# main_board.net
KiCad netlist of a schematic drawn in EAGLE
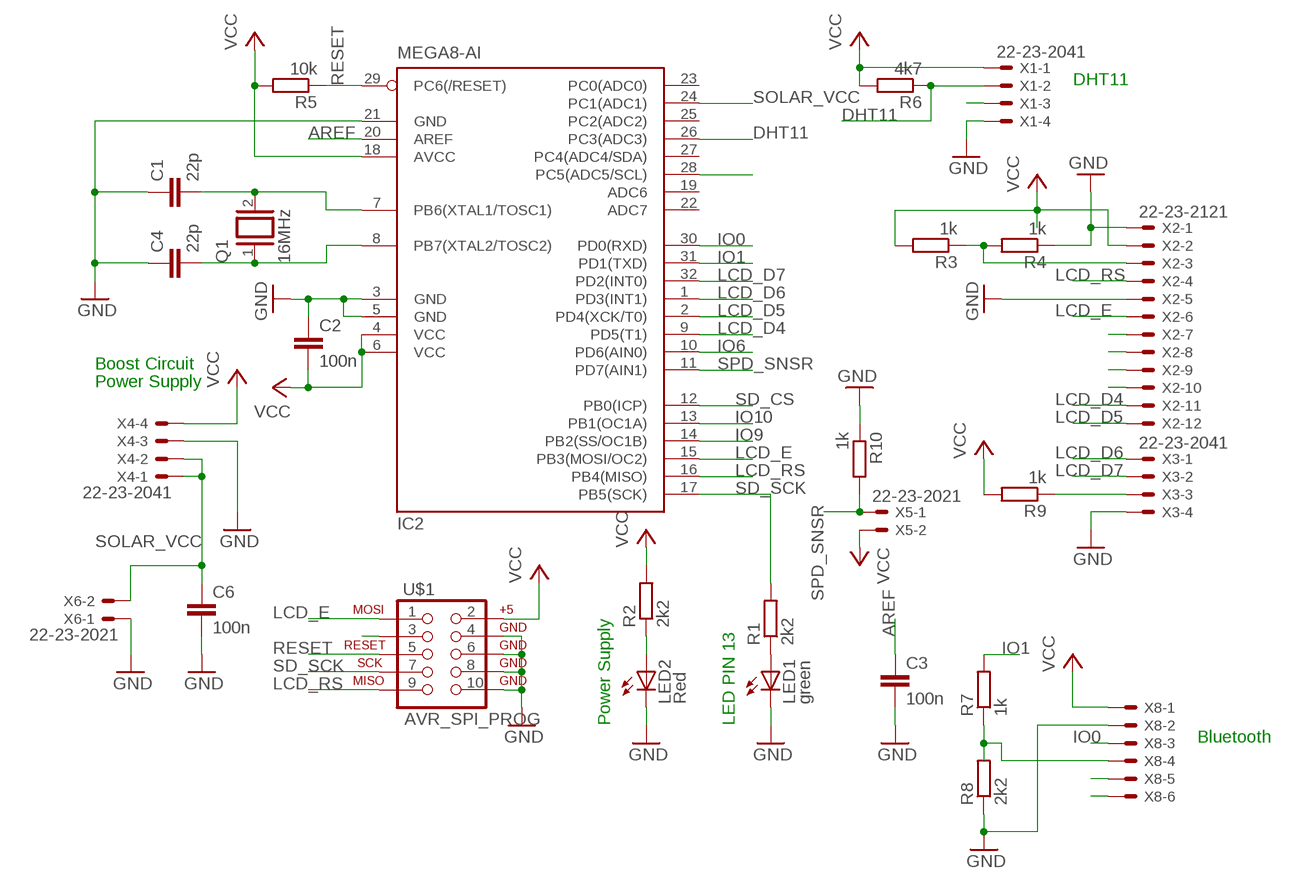
[diagram p0: schematic, sheet 1]

(export (version "E")
  (design (tool "Eeschema 10.0.6"))
  (components
    (comp (ref "C1")
      (value "22p")
      (footprint "eagle-import:C2.5-3")
      (libsource (lib "eagle-import") (part "C2,5-3"))
    )
    (comp (ref "C2")
      (value "100n")
      (footprint "eagle-import:C5B3")
      (libsource (lib "eagle-import") (part "C5/3"))
    )
    (comp (ref "C3")
      (value "100n")
      (footprint "eagle-import:C5B3")
      (libsource (lib "eagle-import") (part "C5/3"))
    )
    (comp (ref "C4")
      (value "22p")
      (footprint "eagle-import:C2.5-3")
      (libsource (lib "eagle-import") (part "C2,5-3"))
    )
    (comp (ref "C6")
      (value "100n")
      (footprint "eagle-import:C7.5B6")
      (libsource (lib "eagle-import") (part "C7.5/6"))
    )
    (comp (ref "IC2")
      (value "MEGA8-AI")
      (footprint "eagle-import:TQFP32-08")
      (fields (field (name "MPN") "ATMEGA8-16AU"))
      (libsource (lib "eagle-import") (part "MEGA8-AI"))
    )
    (comp (ref "LED1")
      (value "green")
      (footprint "eagle-import:LED3MM")
      (libsource (lib "eagle-import") (part "LED3MM"))
    )
    (comp (ref "LED2")
      (value "Red")
      (footprint "eagle-import:LED3MM")
      (libsource (lib "eagle-import") (part "LED3MM"))
    )
    (comp (ref "Q1")
      (value "16MHz")
      (footprint "eagle-import:QS")
      (libsource (lib "eagle-import") (part "XTAL/S"))
    )
    (comp (ref "R1")
      (value "2k2")
      (footprint "eagle-import:0204V")
      (libsource (lib "eagle-import") (part "R-EU_0204/2V"))
    )
    (comp (ref "R2")
      (value "2k2")
      (footprint "eagle-import:0204V")
      (libsource (lib "eagle-import") (part "R-EU_0204/2V"))
    )
    (comp (ref "R3")
      (value "1k")
      (footprint "eagle-import:0204V")
      (libsource (lib "eagle-import") (part "R-EU_0204/2V"))
    )
    (comp (ref "R4")
      (value "1k")
      (footprint "eagle-import:0204V")
      (libsource (lib "eagle-import") (part "R-EU_0204/2V"))
    )
    (comp (ref "R5")
      (value "10k")
      (footprint "eagle-import:0204V")
      (libsource (lib "eagle-import") (part "R-EU_0204/2V"))
    )
    (comp (ref "R6")
      (value "4k7")
      (footprint "eagle-import:0204V")
      (libsource (lib "eagle-import") (part "R-EU_0204/2V"))
    )
    (comp (ref "R7")
      (value "1k")
      (footprint "eagle-import:0204V")
      (libsource (lib "eagle-import") (part "R-EU_0204/2V"))
    )
    (comp (ref "R8")
      (value "2k2")
      (footprint "eagle-import:0204V")
      (libsource (lib "eagle-import") (part "R-EU_0204/2V"))
    )
    (comp (ref "R9")
      (value "1k")
      (footprint "eagle-import:0204V")
      (libsource (lib "eagle-import") (part "R-EU_0204/2V"))
    )
    (comp (ref "R10")
      (value "1k")
      (footprint "eagle-import:0204V")
      (libsource (lib "eagle-import") (part "R-EU_0204/2V"))
    )
    (comp (ref "U$1")
      (value "AVR_SPI_PROG")
      (footprint "eagle-import:AVR_ICSP")
      (libsource (lib "eagle-import") (part "AVR_SPI_PROG"))
    )
    (comp (ref "X1")
      (value "22-23-2041")
      (footprint "eagle-import:22-23-2041")
      (fields (field (name "MF") "MOLEX"))
      (libsource (lib "eagle-import") (part "22-23-2041"))
    )
    (comp (ref "X2")
      (value "22-23-2121")
      (footprint "eagle-import:22-23-2121")
      (fields (field (name "MF") "MOLEX"))
      (libsource (lib "eagle-import") (part "22-23-2121"))
    )
    (comp (ref "X3")
      (value "22-23-2041")
      (footprint "eagle-import:22-23-2041")
      (fields (field (name "MF") "MOLEX"))
      (libsource (lib "eagle-import") (part "22-23-2041"))
    )
    (comp (ref "X4")
      (value "22-23-2041")
      (footprint "eagle-import:22-23-2041")
      (fields (field (name "MF") "MOLEX"))
      (libsource (lib "eagle-import") (part "22-23-2041"))
    )
    (comp (ref "X5")
      (value "22-23-2021")
      (footprint "eagle-import:22-23-2021")
      (fields (field (name "MF") "MOLEX"))
      (libsource (lib "eagle-import") (part "22-23-2021"))
    )
    (comp (ref "X6")
      (value "22-23-2021")
      (footprint "eagle-import:22-23-2021")
      (fields (field (name "MF") "MOLEX"))
      (libsource (lib "eagle-import") (part "22-23-2021"))
    )
    (comp (ref "X8")
      (value "22-23-2061")
      (footprint "eagle-import:22-23-2061")
      (fields (field (name "MF") "MOLEX"))
      (libsource (lib "eagle-import") (part "22-23-2061"))
    )
  )
  (nets
    (net (code "1") (name "/AREF") (class "Default")
      (node (ref "C3") (pin "1") (pinfunction "1_1") (pintype "passive"))
      (node (ref "IC2") (pin "20") (pinfunction "AREF_20") (pintype "passive"))
    )
    (net (code "2") (name "/DHT11") (class "Default")
      (node (ref "IC2") (pin "26") (pinfunction "PC3(ADC3)_26") (pintype "bidirectional"))
      (node (ref "R6") (pin "1") (pinfunction "1_1") (pintype "passive"))
      (node (ref "X1") (pin "2") (pinfunction "S_2") (pintype "passive"))
    )
    (net (code "3") (name "/IO0") (class "Default")
      (node (ref "IC2") (pin "30") (pinfunction "PD0(RXD)_30") (pintype "bidirectional"))
      (node (ref "X8") (pin "3") (pinfunction "S_3") (pintype "passive"))
    )
    (net (code "4") (name "/IO1") (class "Default")
      (node (ref "IC2") (pin "31") (pinfunction "PD1(TXD)_31") (pintype "bidirectional"))
      (node (ref "R7") (pin "2") (pinfunction "2_2") (pintype "passive"))
    )
    (net (code "5") (name "/IO6") (class "Default")
      (node (ref "IC2") (pin "10") (pinfunction "PD6(AIN0)_10") (pintype "bidirectional"))
    )
    (net (code "6") (name "/IO9") (class "Default")
      (node (ref "IC2") (pin "14") (pinfunction "PB2(SS/OC1B)_14") (pintype "bidirectional"))
    )
    (net (code "7") (name "/IO10") (class "Default")
      (node (ref "IC2") (pin "13") (pinfunction "PB1(OC1A)_13") (pintype "bidirectional"))
    )
    (net (code "8") (name "/LCD_D4") (class "Default")
      (node (ref "IC2") (pin "9") (pinfunction "PD5(T1)_9") (pintype "bidirectional"))
      (node (ref "X2") (pin "11") (pinfunction "S_11") (pintype "passive"))
    )
    (net (code "9") (name "/LCD_D5") (class "Default")
      (node (ref "IC2") (pin "2") (pinfunction "PD4(XCK/T0)_2") (pintype "bidirectional"))
      (node (ref "X2") (pin "12") (pinfunction "S_12") (pintype "passive"))
    )
    (net (code "10") (name "/LCD_D6") (class "Default")
      (node (ref "IC2") (pin "1") (pinfunction "PD3(INT1)_1") (pintype "bidirectional"))
      (node (ref "X3") (pin "1") (pinfunction "S_1") (pintype "passive"))
    )
    (net (code "11") (name "/LCD_D7") (class "Default")
      (node (ref "IC2") (pin "32") (pinfunction "PD2(INT0)_32") (pintype "bidirectional"))
      (node (ref "X3") (pin "2") (pinfunction "S_2") (pintype "passive"))
    )
    (net (code "12") (name "/LCD_E") (class "Default")
      (node (ref "IC2") (pin "15") (pinfunction "PB3(MOSI/OC2)_15") (pintype "bidirectional"))
      (node (ref "U$1") (pin "1") (pinfunction "1_1") (pintype "passive"))
      (node (ref "X2") (pin "6") (pinfunction "S_6") (pintype "passive"))
    )
    (net (code "13") (name "/LCD_RS") (class "Default")
      (node (ref "IC2") (pin "16") (pinfunction "PB4(MISO)_16") (pintype "bidirectional"))
      (node (ref "U$1") (pin "9") (pinfunction "9_9") (pintype "passive"))
      (node (ref "X2") (pin "4") (pinfunction "S_4") (pintype "passive"))
    )
    (net (code "14") (name "/RESET") (class "Default")
      (node (ref "IC2") (pin "29") (pinfunction "PC6(/RESET)_29") (pintype "bidirectional"))
      (node (ref "R5") (pin "1") (pinfunction "1_1") (pintype "passive"))
      (node (ref "U$1") (pin "5") (pinfunction "5_5") (pintype "passive"))
    )
    (net (code "15") (name "/SD_CS") (class "Default")
      (node (ref "IC2") (pin "12") (pinfunction "PB0(ICP)_12") (pintype "bidirectional"))
    )
    (net (code "16") (name "/SD_SCK") (class "Default")
      (node (ref "IC2") (pin "17") (pinfunction "PB5(SCK)_17") (pintype "bidirectional"))
      (node (ref "R1") (pin "2") (pinfunction "2_2") (pintype "passive"))
      (node (ref "U$1") (pin "7") (pinfunction "7_7") (pintype "passive"))
    )
    (net (code "17") (name "/SOLAR_VCC") (class "Default")
      (node (ref "C6") (pin "1") (pinfunction "1_1") (pintype "passive"))
      (node (ref "IC2") (pin "24") (pinfunction "PC1(ADC1)_24") (pintype "bidirectional"))
      (node (ref "X4") (pin "1") (pinfunction "S_1") (pintype "passive"))
      (node (ref "X4") (pin "2") (pinfunction "S_2") (pintype "passive"))
      (node (ref "X6") (pin "2") (pinfunction "S_2") (pintype "passive"))
    )
    (net (code "18") (name "/SPD_SNSR") (class "Default")
      (node (ref "IC2") (pin "11") (pinfunction "PD7(AIN1)_11") (pintype "bidirectional"))
      (node (ref "R10") (pin "2") (pinfunction "2_2") (pintype "passive"))
      (node (ref "X5") (pin "1") (pinfunction "S_1") (pintype "passive"))
    )
    (net (code "19") (name "GND") (class "Default")
      (node (ref "C1") (pin "1") (pinfunction "1_1") (pintype "passive"))
      (node (ref "C2") (pin "1") (pinfunction "1_1") (pintype "passive"))
      (node (ref "C3") (pin "2") (pinfunction "2_2") (pintype "passive"))
      (node (ref "C4") (pin "1") (pinfunction "1_1") (pintype "passive"))
      (node (ref "C6") (pin "2") (pinfunction "2_2") (pintype "passive"))
      (node (ref "IC2") (pin "21") (pinfunction "GND_21") (pintype "power_in"))
      (node (ref "IC2") (pin "3") (pinfunction "GND_3") (pintype "power_in"))
      (node (ref "IC2") (pin "5") (pinfunction "GND_5") (pintype "power_in"))
      (node (ref "LED1") (pin "K") (pinfunction "C_K") (pintype "passive"))
      (node (ref "LED2") (pin "K") (pinfunction "C_K") (pintype "passive"))
      (node (ref "R10") (pin "1") (pinfunction "1_1") (pintype "passive"))
      (node (ref "R4") (pin "1") (pinfunction "1_1") (pintype "passive"))
      (node (ref "R8") (pin "1") (pinfunction "1_1") (pintype "passive"))
      (node (ref "U$1") (pin "10") (pinfunction "10_10") (pintype "passive"))
      (node (ref "U$1") (pin "4") (pinfunction "4_4") (pintype "passive"))
      (node (ref "U$1") (pin "6") (pinfunction "6_6") (pintype "passive"))
      (node (ref "U$1") (pin "8") (pinfunction "8_8") (pintype "passive"))
      (node (ref "X1") (pin "4") (pinfunction "S_4") (pintype "passive"))
      (node (ref "X2") (pin "1") (pinfunction "S_1") (pintype "passive"))
      (node (ref "X2") (pin "5") (pinfunction "S_5") (pintype "passive"))
      (node (ref "X3") (pin "4") (pinfunction "S_4") (pintype "passive"))
      (node (ref "X4") (pin "3") (pinfunction "S_3") (pintype "passive"))
      (node (ref "X6") (pin "1") (pinfunction "S_1") (pintype "passive"))
      (node (ref "X8") (pin "2") (pinfunction "S_2") (pintype "passive"))
    )
    (net (code "20") (name "Net-(IC2-PB6(XTAL1{slash}TOSC1))") (class "Default")
      (node (ref "C1") (pin "2") (pinfunction "2_2") (pintype "passive"))
      (node (ref "IC2") (pin "7") (pinfunction "PB6(XTAL1/TOSC1)_7") (pintype "bidirectional"))
      (node (ref "Q1") (pin "2") (pinfunction "2_2") (pintype "passive"))
    )
    (net (code "21") (name "Net-(IC2-PB7(XTAL2{slash}TOSC2))") (class "Default")
      (node (ref "C4") (pin "2") (pinfunction "2_2") (pintype "passive"))
      (node (ref "IC2") (pin "8") (pinfunction "PB7(XTAL2/TOSC2)_8") (pintype "bidirectional"))
      (node (ref "Q1") (pin "1") (pinfunction "1_1") (pintype "passive"))
    )
    (net (code "22") (name "Net-(LED1-PadA)") (class "Default")
      (node (ref "LED1") (pin "A") (pinfunction "A_A") (pintype "passive"))
      (node (ref "R1") (pin "1") (pinfunction "1_1") (pintype "passive"))
    )
    (net (code "23") (name "Net-(LED2-PadA)") (class "Default")
      (node (ref "LED2") (pin "A") (pinfunction "A_A") (pintype "passive"))
      (node (ref "R2") (pin "1") (pinfunction "1_1") (pintype "passive"))
    )
    (net (code "24") (name "Net-(X2F-S)") (class "Default")
      (node (ref "R3") (pin "1") (pinfunction "1_1") (pintype "passive"))
      (node (ref "R4") (pin "2") (pinfunction "2_2") (pintype "passive"))
      (node (ref "X2") (pin "3") (pinfunction "S_3") (pintype "passive"))
    )
    (net (code "25") (name "Net-(X3C-S)") (class "Default")
      (node (ref "R9") (pin "1") (pinfunction "1_1") (pintype "passive"))
      (node (ref "X3") (pin "3") (pinfunction "S_3") (pintype "passive"))
    )
    (net (code "26") (name "Net-(X8D-S)") (class "Default")
      (node (ref "R7") (pin "1") (pinfunction "1_1") (pintype "passive"))
      (node (ref "R8") (pin "2") (pinfunction "2_2") (pintype "passive"))
      (node (ref "X8") (pin "4") (pinfunction "S_4") (pintype "passive"))
    )
    (net (code "27") (name "VCC") (class "Default")
      (node (ref "C2") (pin "2") (pinfunction "2_2") (pintype "passive"))
      (node (ref "IC2") (pin "18") (pinfunction "AVCC_18") (pintype "power_in"))
      (node (ref "IC2") (pin "4") (pinfunction "VCC_4") (pintype "power_in"))
      (node (ref "IC2") (pin "6") (pinfunction "VCC_6") (pintype "power_in"))
      (node (ref "R2") (pin "2") (pinfunction "2_2") (pintype "passive"))
      (node (ref "R3") (pin "2") (pinfunction "2_2") (pintype "passive"))
      (node (ref "R5") (pin "2") (pinfunction "2_2") (pintype "passive"))
      (node (ref "R6") (pin "2") (pinfunction "2_2") (pintype "passive"))
      (node (ref "R9") (pin "2") (pinfunction "2_2") (pintype "passive"))
      (node (ref "U$1") (pin "2") (pinfunction "2_2") (pintype "passive"))
      (node (ref "X1") (pin "1") (pinfunction "S_1") (pintype "passive"))
      (node (ref "X2") (pin "2") (pinfunction "S_2") (pintype "passive"))
      (node (ref "X4") (pin "4") (pinfunction "S_4") (pintype "passive"))
      (node (ref "X5") (pin "2") (pinfunction "S_2") (pintype "passive"))
      (node (ref "X8") (pin "1") (pinfunction "S_1") (pintype "passive"))
    )
    (net (code "28") (name "unconnected-(IC2-ADC6-Pad19)") (class "Default")
      (node (ref "IC2") (pin "19") (pinfunction "ADC6_19") (pintype "bidirectional"))
    )
    (net (code "29") (name "unconnected-(IC2-ADC7-Pad22)") (class "Default")
      (node (ref "IC2") (pin "22") (pinfunction "ADC7_22") (pintype "bidirectional"))
    )
    (net (code "30") (name "unconnected-(IC2-PC0(ADC0)-Pad23)") (class "Default")
      (node (ref "IC2") (pin "23") (pinfunction "PC0(ADC0)_23") (pintype "bidirectional"))
    )
    (net (code "31") (name "unconnected-(IC2-PC2(ADC2)-Pad25)") (class "Default")
      (node (ref "IC2") (pin "25") (pinfunction "PC2(ADC2)_25") (pintype "bidirectional"))
    )
    (net (code "32") (name "unconnected-(IC2-PC4(ADC4{slash}SDA)-Pad27)") (class "Default")
      (node (ref "IC2") (pin "27") (pinfunction "PC4(ADC4/SDA)_27") (pintype "bidirectional"))
    )
    (net (code "33") (name "unconnected-(IC2-PC5(ADC5{slash}SCL)-Pad28)") (class "Default")
      (node (ref "IC2") (pin "28") (pinfunction "PC5(ADC5/SCL)_28") (pintype "bidirectional"))
    )
    (net (code "34") (name "unconnected-(U$1-Pad3)") (class "Default")
      (node (ref "U$1") (pin "3") (pinfunction "3_3") (pintype "passive"))
    )
    (net (code "35") (name "unconnected-(X1C-S-Pad3)") (class "Default")
      (node (ref "X1") (pin "3") (pinfunction "S_3") (pintype "passive"))
    )
    (net (code "36") (name "unconnected-(X2B-S-Pad10)") (class "Default")
      (node (ref "X2") (pin "10") (pinfunction "S_10") (pintype "passive"))
    )
    (net (code "37") (name "unconnected-(X2J-S-Pad7)") (class "Default")
      (node (ref "X2") (pin "7") (pinfunction "S_7") (pintype "passive"))
    )
    (net (code "38") (name "unconnected-(X2K-S-Pad8)") (class "Default")
      (node (ref "X2") (pin "8") (pinfunction "S_8") (pintype "passive"))
    )
    (net (code "39") (name "unconnected-(X2L-S-Pad9)") (class "Default")
      (node (ref "X2") (pin "9") (pinfunction "S_9") (pintype "passive"))
    )
    (net (code "40") (name "unconnected-(X8E-S-Pad5)") (class "Default")
      (node (ref "X8") (pin "5") (pinfunction "S_5") (pintype "passive"))
    )
    (net (code "41") (name "unconnected-(X8F-S-Pad6)") (class "Default")
      (node (ref "X8") (pin "6") (pinfunction "S_6") (pintype "passive"))
    )
  )
)
